# Power_Supply.net
KiCad netlist of a schematic drawn in Altium Designer
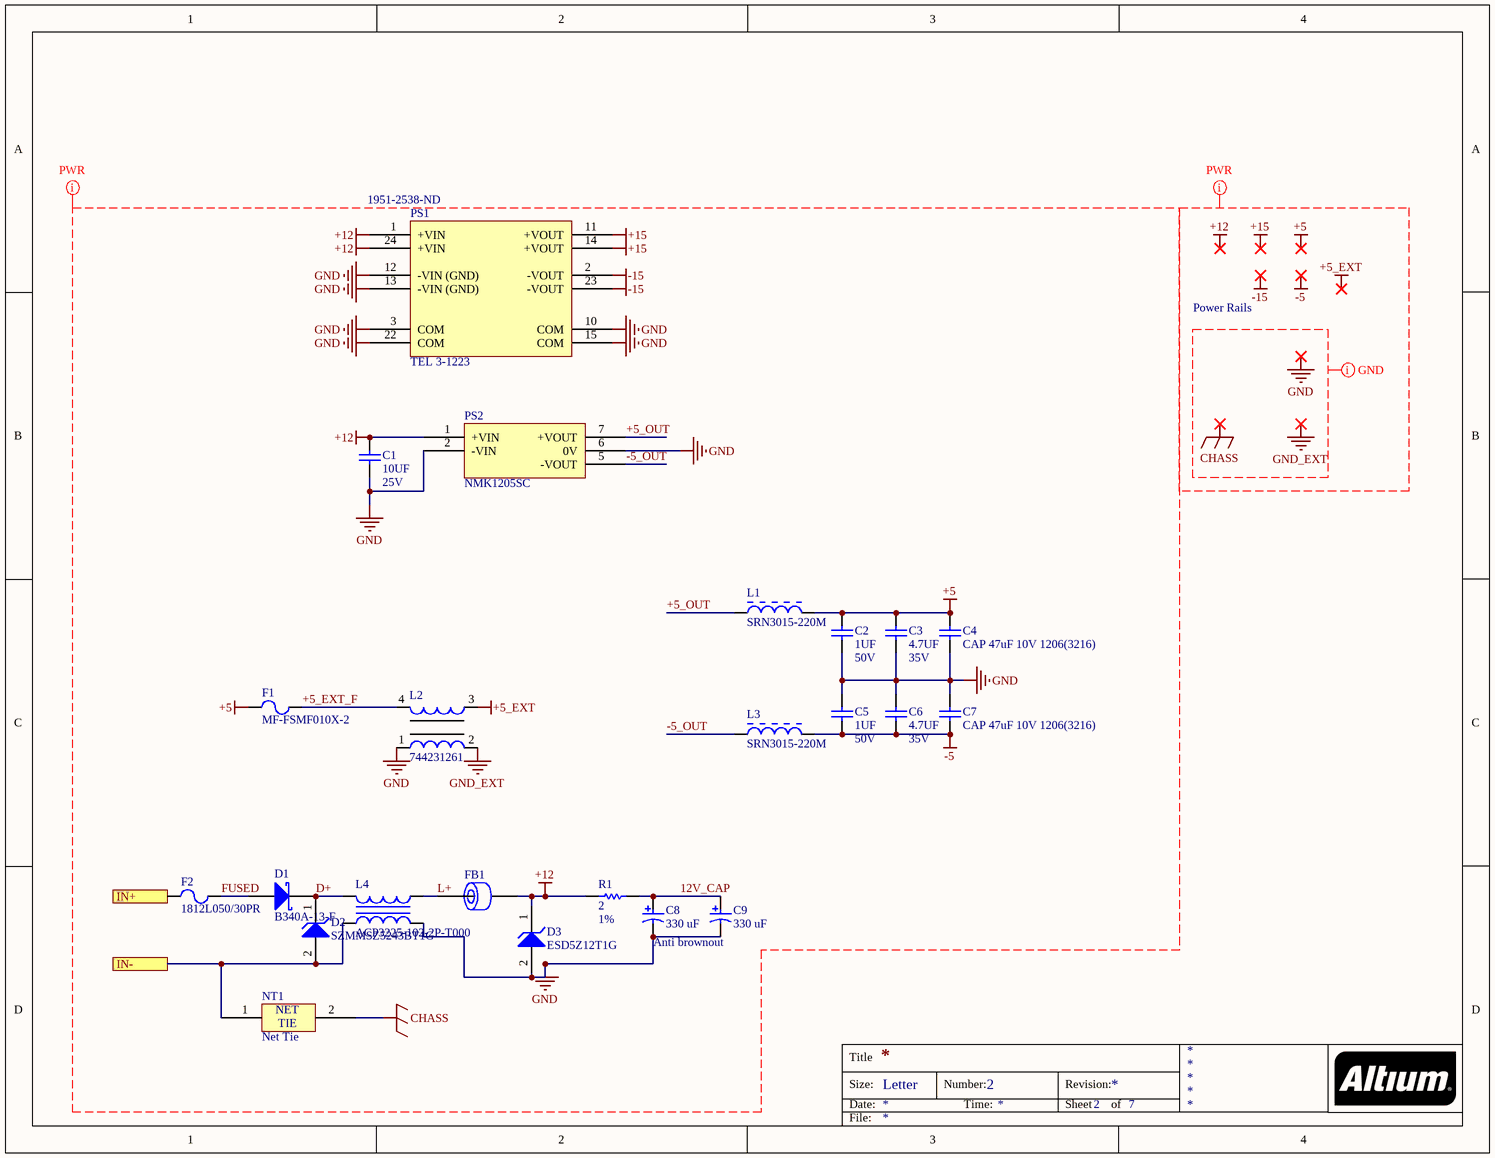
[diagram p0: Power Supply.SchDoc]

(export (version "E")
  (design (tool "Eeschema 10.0.6"))
  (components
    (comp (ref "C1")
      (value "CAP 0603 10UF 25V 20% X5R")
      (footprint "0603_CAP")
      (description "Capacitor Surface Mount 0603 Footprint 10UF 25V 20% Tolerance Ceramic X5R")
      (fields
        (field (name "VAL") "10UF")
        (field (name "VOL") "25V")
        (field (name "MANUFACTURER") "Various")
        (field (name "VOLTAGE") "25V")
      )
      (libsource (lib "Passive Components") (part "cap"))
    )
    (comp (ref "C2")
      (value "CAP 0603 1UF 50V 10% X7R")
      (footprint "0603_CAP")
      (description "Capacitor Surface Mount 0603 Footprint 1UF 50V 10% Tolerance Ceramic X7R")
      (fields
        (field (name "VAL") "1UF")
        (field (name "VOL") "50V")
        (field (name "MANUFACTURER") "Various")
        (field (name "VOLTAGE") "50V")
      )
      (libsource (lib "Passive Components") (part "cap"))
    )
    (comp (ref "C3")
      (value "CAP 0805 4.7UF 35V 10% X7R")
      (footprint "0805_CAP")
      (description "Capacitor Surface Mount 0805 Footprint 4.7UF 35V 10% Tolerance Ceramic X7R")
      (fields
        (field (name "VAL") "4.7UF")
        (field (name "VOL") "35V")
        (field (name "MANUFACTURER") "Various")
        (field (name "VOLTAGE") "35V")
      )
      (libsource (lib "Passive Components") (part "cap"))
    )
    (comp (ref "C4")
      (value "CAP 47uF 10V 1206(3216)")
      (footprint "CAPC1206(3216)190_N")
      (description "CAP 47uF 10V ±20% 1206 (3216 Metric) Thickness 1.9mm SMD")
      (fields (field (name "TOLERANCE") "Â±20%"))
      (libsource (lib "Altium Content Vault") (part "CAP"))
    )
    (comp (ref "C5")
      (value "CAP 0603 1UF 50V 10% X7R")
      (footprint "0603_CAP")
      (description "Capacitor Surface Mount 0603 Footprint 1UF 50V 10% Tolerance Ceramic X7R")
      (fields
        (field (name "VAL") "1UF")
        (field (name "VOL") "50V")
        (field (name "MANUFACTURER") "Various")
        (field (name "VOLTAGE") "50V")
      )
      (libsource (lib "Passive Components") (part "cap"))
    )
    (comp (ref "C6")
      (value "CAP 0805 4.7UF 35V 10% X7R")
      (footprint "0805_CAP")
      (description "Capacitor Surface Mount 0805 Footprint 4.7UF 35V 10% Tolerance Ceramic X7R")
      (fields
        (field (name "VAL") "4.7UF")
        (field (name "VOL") "35V")
        (field (name "MANUFACTURER") "Various")
        (field (name "VOLTAGE") "35V")
      )
      (libsource (lib "Passive Components") (part "cap"))
    )
    (comp (ref "C7")
      (value "CAP 47uF 10V 1206(3216)")
      (footprint "CAPC1206(3216)190_N")
      (description "CAP 47uF 10V ±20% 1206 (3216 Metric) Thickness 1.9mm SMD")
      (fields (field (name "TOLERANCE") "Â±20%"))
      (libsource (lib "Altium Content Vault") (part "CAP"))
    )
    (comp (ref "C8")
      (value "UUD1V331MNL1GS")
      (footprint "NIC-CAPA2-10X10_V")
      (fields (field (name "MANUFACTURER") "Nichicon") (field (name "RATED CAPACITANCE") "330 uF"))
      (libsource (lib "Altium Content Vault") (part "NIC-CAP-P-2"))
    )
    (comp (ref "C9")
      (value "UUD1V331MNL1GS")
      (footprint "NIC-CAPA2-10X10_V")
      (fields (field (name "MANUFACTURER") "Nichicon") (field (name "RATED CAPACITANCE") "330 uF"))
      (libsource (lib "Altium Content Vault") (part "NIC-CAP-P-2"))
    )
    (comp (ref "D1")
      (value "B340A-13-F")
      (footprint "DIOD-SMA-2_V")
      (libsource (lib "Altium Content Vault") (part "DSKY-AK-2"))
    )
    (comp (ref "D2")
      (value "SZMMSZ5243BT1G")
      (footprint "ONSC-SOD-123-2-425-04_V")
      (description "Zener Voltage Regulator, 500 mW, 2-Pin SOD-123, Pb-Free, Tape and Reel")
      (fields (field (name "MANUFACTURER") "On Semiconductor"))
      (libsource (lib "Altium Content Vault") (part "ONSC-K1A2-2"))
    )
    (comp (ref "D3")
      (value "ESD5Z12T1G")
      (footprint "ONSC-SOD-523-2-502-01_V")
      (fields (field (name "MANUFACTURER") "On Semiconductor"))
      (libsource (lib "Altium Content Vault") (part "ONSC-K1A2-2"))
    )
    (comp (ref "F1")
      (value "MF-FSMF010X-2")
      (footprint "MF-FSMF")
      (description "Polymeric PTC Resettable Fuse 15V 100mA Ih Surface Mount 0603 (1608 Metric), Concave")
      (libsource (lib "bspd parts") (part "MF-FSMF010X-2"))
    )
    (comp (ref "F2")
      (value "1812L050/30PR")
      (footprint "LFUS-1812L05030PR_V")
      (description "PTC Resettable Fuse, 0.8 W, 30 V, -40 to 85 degC, 2-Pin SMD, RoHS, Tape and Reel")
      (fields (field (name "MANUFACTURER") "Littelfuse-Inc."))
      (libsource (lib "bspd parts") (part "1812L050/30PR"))
    )
    (comp (ref "FB1")
      (value "Ferrite Chip 1500 Ohms")
      (footprint "0805")
      (description "Ferrite Chip 1000 mA 1500 Ohms Differential Mode - Single 0805 Footprint")
      (fields (field (name "MANUFACTURER") "Wurth Electronics"))
      (libsource (lib "Passive Components") (part "Ferrite Bead"))
    )
    (comp (ref "L1")
      (value "SRN3015-220M")
      (footprint "BOUR-SRN3015-2_V")
      (fields (field (name "MANUFACTURER") "Bourns"))
      (libsource (lib "Altium Content Vault") (part "BOUR-IND-2A"))
    )
    (comp (ref "L2")
      (value "744231261")
      (footprint "WE-CNSW-0805")
      (description "SMD Common Mode Noise Suppressor WE-CNSW, Z = 260 Ohm")
      (libsource (lib "Altium Content Vault") (part "PAS-IND-INDUCTOR-4A"))
    )
    (comp (ref "L3")
      (value "SRN3015-220M")
      (footprint "BOUR-SRN3015-2_V")
      (fields (field (name "MANUFACTURER") "Bourns"))
      (libsource (lib "Altium Content Vault") (part "BOUR-IND-2A"))
    )
    (comp (ref "L4")
      (value "ACP3225-102-2P-T000")
      (footprint "TDK-ACP3225-102-2P-T000-4_V")
      (fields (field (name "MANUFACTURER") "TDK"))
      (libsource (lib "bspd parts") (part "ACP3225-102-2P-T000"))
    )
    (comp (ref "NT1")
      (value "Net Tie")
      (footprint "20MIL_TIE")
      (description "Net Tie (No BOM)")
      (libsource (lib "bspd parts") (part "NET TIE"))
    )
    (comp (ref "PS1")
      (value "TEL 3-1223")
      (footprint "TEL 3-1223")
      (description "Isolated Module DC DC Converter 2 Output 15V -15V   100mA, 100mA 9V - 18V Input")
      (fields (field (name "SUPPLIER PART NUMBER 1") "1951-2538-ND"))
      (libsource (lib "bspd parts") (part "TEL 3-1223"))
    )
    (comp (ref "PS2")
      (value "NMK1205SC")
      (footprint "NMV0505SC")
      (description "Isolated Module DC DC Converter 2 Output 5V -5V   200mA, 200mA 10.8V - 13.2V Input")
      (libsource (lib "bspd parts") (part "NMK1205SC"))
    )
    (comp (ref "R1")
      (value "RES 0805 2 1%")
      (footprint "0805_RES")
      (description "Resistor Surface Mount, 2 Ohms, 0805 Footprint, 1% Tolerance 0.125W")
      (fields
        (field (name "VAL") "2")
        (field (name "TOL") "1%")
        (field (name "MANUFACTURER") "Various")
        (field (name "TOLERANCE") "1%")
      )
      (libsource (lib "Passive Components") (part "res"))
    )
  )
  (nets
    (net (code "1") (name "+5") (class "Default")
      (node (ref "C2") (pin "2") (pinfunction "2_2") (pintype "passive"))
      (node (ref "C3") (pin "2") (pinfunction "2_2") (pintype "passive"))
      (node (ref "C4") (pin "2") (pinfunction "2_2") (pintype "passive"))
      (node (ref "F1") (pin "1") (pinfunction "1_1") (pintype "passive"))
      (node (ref "L1") (pin "2") (pinfunction "2_2") (pintype "passive"))
    )
    (net (code "2") (name "+5_EXT") (class "Default")
      (node (ref "L2") (pin "3") (pinfunction "3_3") (pintype "passive"))
    )
    (net (code "3") (name "+12") (class "Default")
      (node (ref "C1") (pin "2") (pinfunction "2_2") (pintype "passive"))
      (node (ref "D3") (pin "1") (pinfunction "K_1") (pintype "passive"))
      (node (ref "FB1") (pin "2") (pinfunction "2_2") (pintype "passive"))
      (node (ref "PS1") (pin "1") (pinfunction "+VIN_1") (pintype "power_in"))
      (node (ref "PS1") (pin "24") (pinfunction "+VIN_24") (pintype "power_in"))
      (node (ref "PS2") (pin "1") (pinfunction "+VIN_1") (pintype "power_in"))
      (node (ref "R1") (pin "1") (pinfunction "1_1") (pintype "passive"))
    )
    (net (code "4") (name "+15") (class "Default")
      (node (ref "PS1") (pin "11") (pinfunction "+VOUT_11") (pintype "power_in"))
      (node (ref "PS1") (pin "14") (pinfunction "+VOUT_14") (pintype "power_in"))
    )
    (net (code "5") (name "-5") (class "Default")
      (node (ref "C5") (pin "1") (pinfunction "1_1") (pintype "passive"))
      (node (ref "C6") (pin "1") (pinfunction "1_1") (pintype "passive"))
      (node (ref "C7") (pin "1") (pinfunction "1_1") (pintype "passive"))
      (node (ref "L3") (pin "2") (pinfunction "2_2") (pintype "passive"))
    )
    (net (code "6") (name "-15") (class "Default")
      (node (ref "PS1") (pin "2") (pinfunction "-VOUT_2") (pintype "power_in"))
      (node (ref "PS1") (pin "23") (pinfunction "-VOUT_23") (pintype "power_in"))
    )
    (net (code "7") (name "/+5_EXT_F") (class "Default")
      (node (ref "F1") (pin "2") (pinfunction "2_2") (pintype "passive"))
      (node (ref "L2") (pin "4") (pinfunction "4_4") (pintype "passive"))
    )
    (net (code "8") (name "/+5_OUT") (class "Default")
      (node (ref "L1") (pin "1") (pinfunction "1_1") (pintype "passive"))
      (node (ref "PS2") (pin "7") (pinfunction "+VOUT_7") (pintype "power_in"))
    )
    (net (code "9") (name "/-5_OUT") (class "Default")
      (node (ref "L3") (pin "1") (pinfunction "1_1") (pintype "passive"))
      (node (ref "PS2") (pin "5") (pinfunction "-VOUT_5") (pintype "power_in"))
    )
    (net (code "10") (name "/12V_CAP") (class "Default")
      (node (ref "C8") (pin "1") (pinfunction "1_1") (pintype "passive"))
      (node (ref "C9") (pin "1") (pinfunction "1_1") (pintype "passive"))
      (node (ref "R1") (pin "2") (pinfunction "2_2") (pintype "passive"))
    )
    (net (code "11") (name "/D+") (class "Default")
      (node (ref "D1") (pin "2") (pinfunction "K_2") (pintype "passive"))
      (node (ref "D2") (pin "1") (pinfunction "K_1") (pintype "passive"))
      (node (ref "L4") (pin "1") (pinfunction "1_1") (pintype "passive"))
    )
    (net (code "12") (name "/FUSED") (class "Default")
      (node (ref "D1") (pin "1") (pinfunction "A_1") (pintype "passive"))
      (node (ref "F2") (pin "2") (pinfunction "2_2") (pintype "passive"))
    )
    (net (code "13") (name "/IN+") (class "Default")
      (node (ref "F2") (pin "1") (pinfunction "1_1") (pintype "passive"))
    )
    (net (code "14") (name "/IN-") (class "Default")
      (node (ref "D2") (pin "2") (pinfunction "A_2") (pintype "passive"))
      (node (ref "L4") (pin "2") (pinfunction "2_2") (pintype "passive"))
      (node (ref "NT1") (pin "1") (pintype "passive"))
    )
    (net (code "15") (name "/L+") (class "Default")
      (node (ref "FB1") (pin "1") (pinfunction "1_1") (pintype "passive"))
      (node (ref "L4") (pin "4") (pinfunction "4_4") (pintype "passive"))
    )
    (net (code "16") (name "CHASS") (class "Default") (node (ref "NT1") (pin "2") (pintype "passive")))
    (net (code "17") (name "GND") (class "Default")
      (node (ref "C1") (pin "1") (pinfunction "1_1") (pintype "passive"))
      (node (ref "C2") (pin "1") (pinfunction "1_1") (pintype "passive"))
      (node (ref "C3") (pin "1") (pinfunction "1_1") (pintype "passive"))
      (node (ref "C4") (pin "1") (pinfunction "1_1") (pintype "passive"))
      (node (ref "C5") (pin "2") (pinfunction "2_2") (pintype "passive"))
      (node (ref "C6") (pin "2") (pinfunction "2_2") (pintype "passive"))
      (node (ref "C7") (pin "2") (pinfunction "2_2") (pintype "passive"))
      (node (ref "C8") (pin "2") (pinfunction "2_2") (pintype "passive"))
      (node (ref "C9") (pin "2") (pinfunction "2_2") (pintype "passive"))
      (node (ref "D3") (pin "2") (pinfunction "A_2") (pintype "passive"))
      (node (ref "L2") (pin "1") (pinfunction "1_1") (pintype "passive"))
      (node (ref "L4") (pin "3") (pinfunction "3_3") (pintype "passive"))
      (node (ref "PS1") (pin "10") (pinfunction "COM_10") (pintype "power_in"))
      (node (ref "PS1") (pin "12") (pinfunction "-VIN_(GND)_12") (pintype "power_in"))
      (node (ref "PS1") (pin "13") (pinfunction "-VIN_(GND)_13") (pintype "power_in"))
      (node (ref "PS1") (pin "15") (pinfunction "COM_15") (pintype "power_in"))
      (node (ref "PS1") (pin "22") (pinfunction "COM_22") (pintype "power_in"))
      (node (ref "PS1") (pin "3") (pinfunction "COM_3") (pintype "power_in"))
      (node (ref "PS2") (pin "2") (pinfunction "-VIN_2") (pintype "power_in"))
      (node (ref "PS2") (pin "6") (pinfunction "0V_6") (pintype "power_in"))
    )
    (net (code "18") (name "GND_EXT") (class "Default")
      (node (ref "L2") (pin "2") (pinfunction "2_2") (pintype "passive"))
    )
  )
)
